# midi_footswitch.net
KiCad netlist of a schematic drawn in EasyEDA Pro
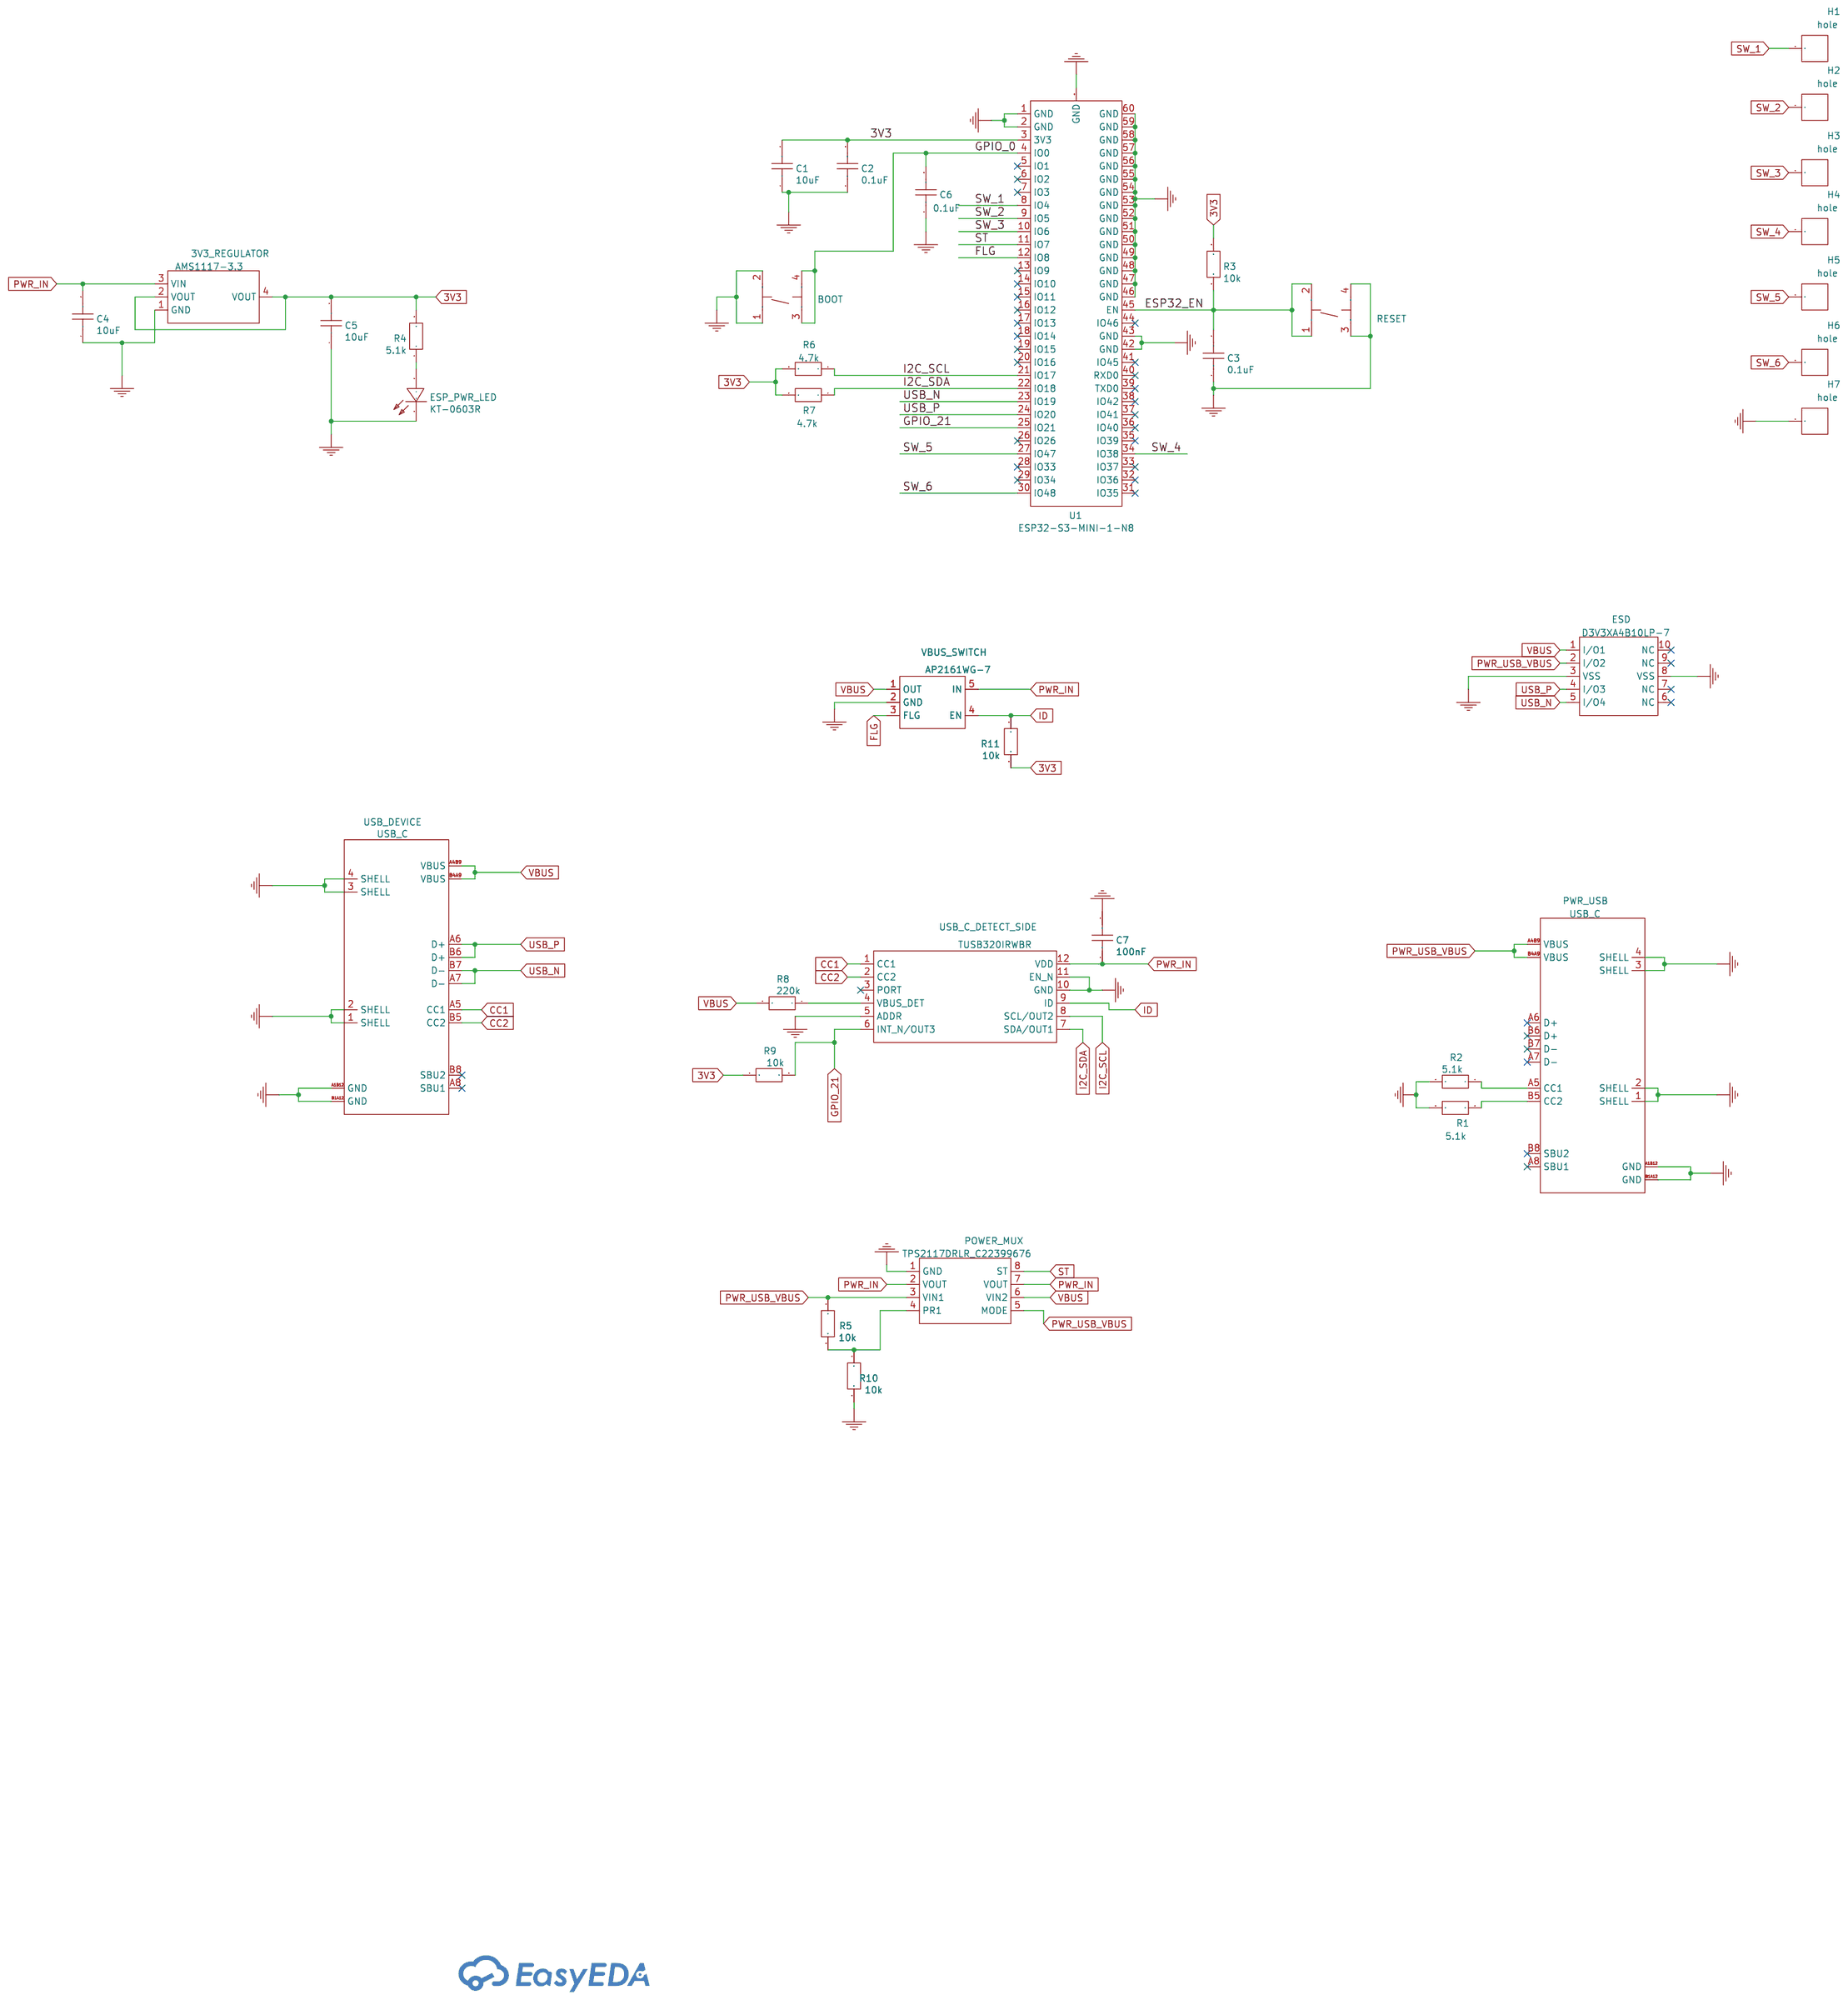
[diagram p0: schematic sheet]

(export (version "E")
  (design (tool "Eeschema 10.0.6"))
  (components
    (comp (ref "3V3_REGULATOR")
      (value "AMS1117-3.3")
      (footprint "easyedapro:SOT-223-3_L6.5-W3.4-P2.30-LS7.0-BR")
      (fields (field (name "Manufacturer") "AMS"))
      (libsource (lib "easyedapro") (part "AMS1117-3.3"))
    )
    (comp (ref "BOOT")
      (value "TS-1187A-B-A-B")
      (footprint "easyedapro:SW-SMD_4P-L5.1-W5.1-P3.70-LS6.5-TL_H1.5")
      (fields (field (name "Manufacturer") "XKB Connectivity(中国星坤)"))
      (libsource (lib "easyedapro") (part "TS-1187A-B-A-B"))
    )
    (comp (ref "C1")
      (value "10uF")
      (footprint "easyedapro:C0603")
      (libsource (lib "easyedapro") (part "10uF"))
    )
    (comp (ref "C2")
      (value "0.1uF")
      (footprint "easyedapro:C0603")
      (libsource (lib "easyedapro") (part "0.1uF"))
    )
    (comp (ref "C3")
      (value "0.1uF")
      (footprint "easyedapro:C0603")
      (libsource (lib "easyedapro") (part "0.1uF"))
    )
    (comp (ref "C4")
      (value "10uF")
      (footprint "easyedapro:C0603")
      (libsource (lib "easyedapro") (part "10uF"))
    )
    (comp (ref "C5")
      (value "10uF")
      (footprint "easyedapro:C0603")
      (libsource (lib "easyedapro") (part "10uF"))
    )
    (comp (ref "C6")
      (value "0.1uF")
      (footprint "easyedapro:C0603")
      (libsource (lib "easyedapro") (part "0.1uF"))
    )
    (comp (ref "C7")
      (value "100nF")
      (footprint "easyedapro:C0603")
      (libsource (lib "easyedapro") (part "100nF"))
    )
    (comp (ref "ESD")
      (value "D3V3XA4B10LP-7")
      (footprint "easyedapro:U-DFN2510-10_L2.5-W1.0-P0.50-BL")
      (fields (field (name "Manufacturer") "DIODES(美台)"))
      (libsource (lib "easyedapro") (part "D3V3XA4B10LP-7"))
    )
    (comp (ref "ESP_PWR_LED")
      (value "KT-0603R")
      (footprint "easyedapro:LED0603-RD")
      (fields (field (name "Manufacturer") "KENTO"))
      (libsource (lib "easyedapro") (part "KT-0603R"))
    )
    (comp (ref "H1")
      (value "hole")
      (footprint "easyedapro:HOLE_FOOTPRITNG")
      (libsource (lib "easyedapro") (part "hole"))
    )
    (comp (ref "H2")
      (value "hole")
      (footprint "easyedapro:HOLE_FOOTPRITNG")
      (libsource (lib "easyedapro") (part "hole"))
    )
    (comp (ref "H3")
      (value "hole")
      (footprint "easyedapro:HOLE_FOOTPRITNG")
      (libsource (lib "easyedapro") (part "hole"))
    )
    (comp (ref "H4")
      (value "hole")
      (footprint "easyedapro:HOLE_FOOTPRITNG")
      (libsource (lib "easyedapro") (part "hole"))
    )
    (comp (ref "H5")
      (value "hole")
      (footprint "easyedapro:HOLE_FOOTPRITNG")
      (libsource (lib "easyedapro") (part "hole"))
    )
    (comp (ref "H6")
      (value "hole")
      (footprint "easyedapro:HOLE_FOOTPRITNG")
      (libsource (lib "easyedapro") (part "hole"))
    )
    (comp (ref "H7")
      (value "hole")
      (footprint "easyedapro:HOLE_FOOTPRITNG")
      (libsource (lib "easyedapro") (part "hole"))
    )
    (comp (ref "POWER_MUX")
      (value "TPS2117DRLR_C22399676")
      (footprint "easyedapro:SOT-583-8_L2.1-W1.2-P0.50-LS1.6-BL")
      (fields (field (name "Manufacturer Part") "TPS2117DRLR") (field (name "Manufacturer") "TI(德州仪器)"))
      (libsource (lib "easyedapro") (part "TPS2117DRLR_C22399676"))
    )
    (comp (ref "PWR_USB")
      (value "USB_C")
      (footprint "easyedapro:USB-C-SMD_G-SWITCH_GT-USB-7010EN")
      (fields
        (field (name "Manufacturer Part") "HC-TYPE-C-16P-01A-R")
        (field (name "Manufacturer") "HCTL(华灿天禄)")
      )
      (libsource (lib "") (part "USB_C_1"))
    )
    (comp (ref "R1")
      (value "5.1k")
      (footprint "easyedapro:R0603")
      (libsource (lib "easyedapro") (part "5.1k"))
    )
    (comp (ref "R2")
      (value "5.1k")
      (footprint "easyedapro:R0603")
      (libsource (lib "easyedapro") (part "5.1k"))
    )
    (comp (ref "R3") (value "10k") (footprint "easyedapro:R0603") (libsource (lib "") (part "10k_1")))
    (comp (ref "R4") (value "5.1k") (footprint "easyedapro:R0603") (libsource (lib "") (part "5.1k_1")))
    (comp (ref "R5") (value "10k") (footprint "easyedapro:R0603") (libsource (lib "easyedapro") (part "10k")))
    (comp (ref "R6")
      (value "4.7k")
      (footprint "easyedapro:R0603")
      (libsource (lib "easyedapro") (part "4.7k"))
    )
    (comp (ref "R7")
      (value "4.7k")
      (footprint "easyedapro:R0603")
      (libsource (lib "easyedapro") (part "4.7k"))
    )
    (comp (ref "R8")
      (value "220k")
      (footprint "easyedapro:R0603")
      (libsource (lib "easyedapro") (part "220k"))
    )
    (comp (ref "R9") (value "10k") (footprint "easyedapro:R0603") (libsource (lib "") (part "10k_2")))
    (comp (ref "R10")
      (value "10k")
      (footprint "easyedapro:R0603")
      (libsource (lib "easyedapro") (part "10k"))
    )
    (comp (ref "R11")
      (value "10k")
      (footprint "easyedapro:R0603")
      (libsource (lib "easyedapro") (part "10k"))
    )
    (comp (ref "RESET")
      (value "TS-1187A-B-A-B")
      (footprint "easyedapro:SW-SMD_4P-L5.1-W5.1-P3.70-LS6.5-TL_H1.5")
      (fields (field (name "Manufacturer") "XKB Connectivity(中国星坤)"))
      (libsource (lib "easyedapro") (part "TS-1187A-B-A-B"))
    )
    (comp (ref "U1")
      (value "ESP32-S3-MINI-1-N8")
      (footprint "easyedapro:BULETM-SMD_ESP32-S3-MINI-1-N8")
      (fields (field (name "Manufacturer") "ESPRESSIF(乐鑫)"))
      (libsource (lib "easyedapro") (part "ESP32-S3-MINI-1-N8"))
    )
    (comp (ref "USB_C_DETECT_SIDE")
      (value "TUSB320IRWBR")
      (footprint "easyedapro:X2QFN-12_L1.6-W1.6-P0.40-TL")
      (fields (field (name "Manufacturer") "TI(德州仪器)"))
      (libsource (lib "easyedapro") (part "TUSB320IRWBR"))
    )
    (comp (ref "USB_DEVICE")
      (value "USB_C")
      (footprint "easyedapro:USB-C-SMD_G-SWITCH_GT-USB-7010EN")
      (fields
        (field (name "Manufacturer Part") "HC-TYPE-C-16P-01A-R")
        (field (name "Manufacturer") "HCTL(华灿天禄)")
      )
      (libsource (lib "easyedapro") (part "USB_C"))
    )
    (comp (ref "VBUS_SWITCH")
      (value "AP2161WG-7")
      (footprint "easyedapro:SOT-23-5_L2.9-W1.6-P0.95-LS2.8-BL")
      (fields (field (name "Manufacturer") "DIODES(美台)"))
      (libsource (lib "easyedapro") (part "AP2161WG-7"))
    )
  )
  (nets
    (net (code "1") (name "/ESP32_EN") (class "Default")
      (node (ref "C3") (pin "2") (pinfunction "2_2") (pintype "unspecified"))
      (node (ref "R3") (pin "1") (pinfunction "1_1") (pintype "unspecified"))
      (node (ref "RESET") (pin "1") (pinfunction "A_1") (pintype "unspecified"))
      (node (ref "RESET") (pin "2") (pinfunction "B_2") (pintype "unspecified"))
      (node (ref "U1") (pin "45") (pinfunction "EN_45") (pintype "unspecified"))
    )
    (net (code "2") (name "/GPIO_0") (class "Default")
      (node (ref "BOOT") (pin "3") (pinfunction "C_3") (pintype "unspecified"))
      (node (ref "BOOT") (pin "4") (pinfunction "D_4") (pintype "unspecified"))
      (node (ref "C6") (pin "2") (pinfunction "2_2") (pintype "unspecified"))
      (node (ref "U1") (pin "4") (pinfunction "IO0_4") (pintype "unspecified"))
    )
    (net (code "3") (name "3V3") (class "Default")
      (node (ref "3V3_REGULATOR") (pin "2") (pinfunction "VOUT_2") (pintype "unspecified"))
      (node (ref "3V3_REGULATOR") (pin "4") (pinfunction "VOUT_4") (pintype "unspecified"))
      (node (ref "C1") (pin "2") (pinfunction "2_2") (pintype "unspecified"))
      (node (ref "C2") (pin "2") (pinfunction "2_2") (pintype "unspecified"))
      (node (ref "C5") (pin "2") (pinfunction "2_2") (pintype "unspecified"))
      (node (ref "R11") (pin "2") (pinfunction "2_2") (pintype "unspecified"))
      (node (ref "R3") (pin "2") (pinfunction "2_2") (pintype "unspecified"))
      (node (ref "R4") (pin "2") (pinfunction "2_2") (pintype "unspecified"))
      (node (ref "R6") (pin "2") (pinfunction "2_2") (pintype "unspecified"))
      (node (ref "R7") (pin "2") (pinfunction "2_2") (pintype "unspecified"))
      (node (ref "R9") (pin "1") (pinfunction "1_1") (pintype "unspecified"))
      (node (ref "U1") (pin "3") (pinfunction "3V3_3") (pintype "unspecified"))
    )
    (net (code "4") (name "CC1") (class "Default")
      (node (ref "USB_C_DETECT_SIDE") (pin "1") (pinfunction "CC1_1") (pintype "unspecified"))
      (node (ref "USB_DEVICE") (pin "A5") (pinfunction "CC1_A5") (pintype "unspecified"))
    )
    (net (code "5") (name "CC2") (class "Default")
      (node (ref "USB_C_DETECT_SIDE") (pin "2") (pinfunction "CC2_2") (pintype "unspecified"))
      (node (ref "USB_DEVICE") (pin "B5") (pinfunction "CC2_B5") (pintype "unspecified"))
    )
    (net (code "6") (name "FLG") (class "Default")
      (node (ref "U1") (pin "12") (pinfunction "IO8_12") (pintype "unspecified"))
      (node (ref "VBUS_SWITCH") (pin "3") (pinfunction "FLG_3") (pintype "unspecified"))
    )
    (net (code "7") (name "GND") (class "Default")
      (node (ref "3V3_REGULATOR") (pin "1") (pinfunction "GND_1") (pintype "unspecified"))
      (node (ref "BOOT") (pin "1") (pinfunction "A_1") (pintype "unspecified"))
      (node (ref "BOOT") (pin "2") (pinfunction "B_2") (pintype "unspecified"))
      (node (ref "C1") (pin "1") (pinfunction "1_1") (pintype "unspecified"))
      (node (ref "C2") (pin "1") (pinfunction "1_1") (pintype "unspecified"))
      (node (ref "C3") (pin "1") (pinfunction "1_1") (pintype "unspecified"))
      (node (ref "C4") (pin "1") (pinfunction "1_1") (pintype "unspecified"))
      (node (ref "C5") (pin "1") (pinfunction "1_1") (pintype "unspecified"))
      (node (ref "C6") (pin "1") (pinfunction "1_1") (pintype "unspecified"))
      (node (ref "C7") (pin "2") (pinfunction "2_2") (pintype "unspecified"))
      (node (ref "ESD") (pin "3") (pinfunction "VSS_3") (pintype "unspecified"))
      (node (ref "ESD") (pin "8") (pinfunction "VSS_8") (pintype "unspecified"))
      (node (ref "ESP_PWR_LED") (pin "1") (pinfunction "K_1") (pintype "unspecified"))
      (node (ref "H7") (pin "1") (pinfunction "1_1") (pintype "bidirectional"))
      (node (ref "POWER_MUX") (pin "1") (pinfunction "GND_1") (pintype "unspecified"))
      (node (ref "PWR_USB") (pin "1") (pinfunction "SHELL_1") (pintype "unspecified"))
      (node (ref "PWR_USB") (pin "2") (pinfunction "SHELL_2") (pintype "unspecified"))
      (node (ref "PWR_USB") (pin "3") (pinfunction "SHELL_3") (pintype "unspecified"))
      (node (ref "PWR_USB") (pin "4") (pinfunction "SHELL_4") (pintype "unspecified"))
      (node (ref "PWR_USB") (pin "A1B12") (pinfunction "GND_A1B12") (pintype "unspecified"))
      (node (ref "PWR_USB") (pin "B1A12") (pinfunction "GND_B1A12") (pintype "unspecified"))
      (node (ref "R1") (pin "2") (pinfunction "2_2") (pintype "unspecified"))
      (node (ref "R10") (pin "2") (pinfunction "2_2") (pintype "unspecified"))
      (node (ref "R2") (pin "2") (pinfunction "2_2") (pintype "unspecified"))
      (node (ref "RESET") (pin "3") (pinfunction "C_3") (pintype "unspecified"))
      (node (ref "RESET") (pin "4") (pinfunction "D_4") (pintype "unspecified"))
      (node (ref "U1") (pin "1") (pinfunction "GND_1") (pintype "unspecified"))
      (node (ref "U1") (pin "2") (pinfunction "GND_2") (pintype "unspecified"))
      (node (ref "U1") (pin "42") (pinfunction "GND_42") (pintype "unspecified"))
      (node (ref "U1") (pin "43") (pinfunction "GND_43") (pintype "unspecified"))
      (node (ref "U1") (pin "46") (pinfunction "GND_46") (pintype "unspecified"))
      (node (ref "U1") (pin "47") (pinfunction "GND_47") (pintype "unspecified"))
      (node (ref "U1") (pin "48") (pinfunction "GND_48") (pintype "unspecified"))
      (node (ref "U1") (pin "49") (pinfunction "GND_49") (pintype "unspecified"))
      (node (ref "U1") (pin "50") (pinfunction "GND_50") (pintype "unspecified"))
      (node (ref "U1") (pin "51") (pinfunction "GND_51") (pintype "unspecified"))
      (node (ref "U1") (pin "52") (pinfunction "GND_52") (pintype "unspecified"))
      (node (ref "U1") (pin "53") (pinfunction "GND_53") (pintype "unspecified"))
      (node (ref "U1") (pin "54") (pinfunction "GND_54") (pintype "unspecified"))
      (node (ref "U1") (pin "55") (pinfunction "GND_55") (pintype "unspecified"))
      (node (ref "U1") (pin "56") (pinfunction "GND_56") (pintype "unspecified"))
      (node (ref "U1") (pin "57") (pinfunction "GND_57") (pintype "unspecified"))
      (node (ref "U1") (pin "58") (pinfunction "GND_58") (pintype "unspecified"))
      (node (ref "U1") (pin "59") (pinfunction "GND_59") (pintype "unspecified"))
      (node (ref "U1") (pin "60") (pinfunction "GND_60") (pintype "unspecified"))
      (node (ref "U1") (pin "GND") (pinfunction "GND_GND") (pintype "unspecified"))
      (node (ref "USB_C_DETECT_SIDE") (pin "10") (pinfunction "GND_10") (pintype "unspecified"))
      (node (ref "USB_C_DETECT_SIDE") (pin "11") (pinfunction "EN_N_11") (pintype "unspecified"))
      (node (ref "USB_C_DETECT_SIDE") (pin "5") (pinfunction "ADDR_5") (pintype "unspecified"))
      (node (ref "USB_DEVICE") (pin "1") (pinfunction "SHELL_1") (pintype "unspecified"))
      (node (ref "USB_DEVICE") (pin "2") (pinfunction "SHELL_2") (pintype "unspecified"))
      (node (ref "USB_DEVICE") (pin "3") (pinfunction "SHELL_3") (pintype "unspecified"))
      (node (ref "USB_DEVICE") (pin "4") (pinfunction "SHELL_4") (pintype "unspecified"))
      (node (ref "USB_DEVICE") (pin "A1B12") (pinfunction "GND_A1B12") (pintype "unspecified"))
      (node (ref "USB_DEVICE") (pin "B1A12") (pinfunction "GND_B1A12") (pintype "unspecified"))
      (node (ref "VBUS_SWITCH") (pin "2") (pinfunction "GND_2") (pintype "unspecified"))
    )
    (net (code "8") (name "GPIO_21") (class "Default")
      (node (ref "R9") (pin "2") (pinfunction "2_2") (pintype "unspecified"))
      (node (ref "U1") (pin "25") (pinfunction "IO21_25") (pintype "unspecified"))
      (node (ref "USB_C_DETECT_SIDE") (pin "6") (pinfunction "INT_N/OUT3_6") (pintype "unspecified"))
    )
    (net (code "9") (name "I2C_SCL") (class "Default")
      (node (ref "R6") (pin "1") (pinfunction "1_1") (pintype "unspecified"))
      (node (ref "U1") (pin "21") (pinfunction "IO17_21") (pintype "unspecified"))
      (node (ref "USB_C_DETECT_SIDE") (pin "8") (pinfunction "SCL/OUT2_8") (pintype "unspecified"))
    )
    (net (code "10") (name "I2C_SDA") (class "Default")
      (node (ref "R7") (pin "1") (pinfunction "1_1") (pintype "unspecified"))
      (node (ref "U1") (pin "22") (pinfunction "IO18_22") (pintype "unspecified"))
      (node (ref "USB_C_DETECT_SIDE") (pin "7") (pinfunction "SDA/OUT1_7") (pintype "unspecified"))
    )
    (net (code "11") (name "ID") (class "Default")
      (node (ref "R11") (pin "1") (pinfunction "1_1") (pintype "unspecified"))
      (node (ref "USB_C_DETECT_SIDE") (pin "9") (pinfunction "ID_9") (pintype "unspecified"))
      (node (ref "VBUS_SWITCH") (pin "4") (pinfunction "EN_4") (pintype "unspecified"))
    )
    (net (code "12") (name "Net-(ESP_PWR_LED-A)") (class "Default")
      (node (ref "ESP_PWR_LED") (pin "2") (pinfunction "A_2") (pintype "unspecified"))
      (node (ref "R4") (pin "1") (pinfunction "1_1") (pintype "unspecified"))
    )
    (net (code "13") (name "Net-(POWER_MUX-PR1)") (class "Default")
      (node (ref "POWER_MUX") (pin "4") (pinfunction "PR1_4") (pintype "unspecified"))
      (node (ref "R10") (pin "1") (pinfunction "1_1") (pintype "unspecified"))
      (node (ref "R5") (pin "2") (pinfunction "2_2") (pintype "unspecified"))
    )
    (net (code "14") (name "Net-(PWR_USB-CC1)") (class "Default")
      (node (ref "PWR_USB") (pin "A5") (pinfunction "CC1_A5") (pintype "unspecified"))
      (node (ref "R2") (pin "1") (pinfunction "1_1") (pintype "unspecified"))
    )
    (net (code "15") (name "Net-(PWR_USB-CC2)") (class "Default")
      (node (ref "PWR_USB") (pin "B5") (pinfunction "CC2_B5") (pintype "unspecified"))
      (node (ref "R1") (pin "1") (pinfunction "1_1") (pintype "unspecified"))
    )
    (net (code "16") (name "Net-(USB_C_DETECT_SIDE-VBUS_DET)") (class "Default")
      (node (ref "R8") (pin "1") (pinfunction "1_1") (pintype "unspecified"))
      (node (ref "USB_C_DETECT_SIDE") (pin "4") (pinfunction "VBUS_DET_4") (pintype "unspecified"))
    )
    (net (code "17") (name "PWR_IN") (class "Default")
      (node (ref "3V3_REGULATOR") (pin "3") (pinfunction "VIN_3") (pintype "unspecified"))
      (node (ref "C4") (pin "2") (pinfunction "2_2") (pintype "unspecified"))
      (node (ref "C7") (pin "1") (pinfunction "1_1") (pintype "unspecified"))
      (node (ref "POWER_MUX") (pin "2") (pinfunction "VOUT_2") (pintype "unspecified"))
      (node (ref "POWER_MUX") (pin "7") (pinfunction "VOUT_7") (pintype "unspecified"))
      (node (ref "USB_C_DETECT_SIDE") (pin "12") (pinfunction "VDD_12") (pintype "unspecified"))
      (node (ref "VBUS_SWITCH") (pin "5") (pinfunction "IN_5") (pintype "unspecified"))
    )
    (net (code "18") (name "PWR_USB_VBUS") (class "Default")
      (node (ref "ESD") (pin "2") (pinfunction "I/O2_2") (pintype "unspecified"))
      (node (ref "POWER_MUX") (pin "3") (pinfunction "VIN1_3") (pintype "unspecified"))
      (node (ref "POWER_MUX") (pin "5") (pinfunction "MODE_5") (pintype "unspecified"))
      (node (ref "PWR_USB") (pin "A4B9") (pinfunction "VBUS_A4B9") (pintype "unspecified"))
      (node (ref "PWR_USB") (pin "B4A9") (pinfunction "VBUS_B4A9") (pintype "unspecified"))
      (node (ref "R5") (pin "1") (pinfunction "1_1") (pintype "unspecified"))
    )
    (net (code "19") (name "ST") (class "Default")
      (node (ref "POWER_MUX") (pin "8") (pinfunction "ST_8") (pintype "unspecified"))
      (node (ref "U1") (pin "11") (pinfunction "IO7_11") (pintype "unspecified"))
    )
    (net (code "20") (name "SW_1") (class "Default")
      (node (ref "H1") (pin "1") (pinfunction "1_1") (pintype "bidirectional"))
      (node (ref "U1") (pin "8") (pinfunction "IO4_8") (pintype "unspecified"))
    )
    (net (code "21") (name "SW_2") (class "Default")
      (node (ref "H2") (pin "1") (pinfunction "1_1") (pintype "bidirectional"))
      (node (ref "U1") (pin "9") (pinfunction "IO5_9") (pintype "unspecified"))
    )
    (net (code "22") (name "SW_3") (class "Default")
      (node (ref "H3") (pin "1") (pinfunction "1_1") (pintype "bidirectional"))
      (node (ref "U1") (pin "10") (pinfunction "IO6_10") (pintype "unspecified"))
    )
    (net (code "23") (name "SW_4") (class "Default")
      (node (ref "H4") (pin "1") (pinfunction "1_1") (pintype "bidirectional"))
      (node (ref "U1") (pin "34") (pinfunction "IO38_34") (pintype "unspecified"))
    )
    (net (code "24") (name "SW_5") (class "Default")
      (node (ref "H5") (pin "1") (pinfunction "1_1") (pintype "bidirectional"))
      (node (ref "U1") (pin "27") (pinfunction "IO47_27") (pintype "unspecified"))
    )
    (net (code "25") (name "SW_6") (class "Default")
      (node (ref "H6") (pin "1") (pinfunction "1_1") (pintype "bidirectional"))
      (node (ref "U1") (pin "30") (pinfunction "IO48_30") (pintype "unspecified"))
    )
    (net (code "26") (name "USB_N") (class "Default")
      (node (ref "ESD") (pin "5") (pinfunction "I/O4_5") (pintype "unspecified"))
      (node (ref "U1") (pin "23") (pinfunction "IO19_23") (pintype "unspecified"))
      (node (ref "USB_DEVICE") (pin "A7") (pinfunction "D-_A7") (pintype "unspecified"))
      (node (ref "USB_DEVICE") (pin "B7") (pinfunction "D-_B7") (pintype "unspecified"))
    )
    (net (code "27") (name "USB_P") (class "Default")
      (node (ref "ESD") (pin "4") (pinfunction "I/O3_4") (pintype "unspecified"))
      (node (ref "U1") (pin "24") (pinfunction "IO20_24") (pintype "unspecified"))
      (node (ref "USB_DEVICE") (pin "A6") (pinfunction "D+_A6") (pintype "unspecified"))
      (node (ref "USB_DEVICE") (pin "B6") (pinfunction "D+_B6") (pintype "unspecified"))
    )
    (net (code "28") (name "VBUS") (class "Default")
      (node (ref "ESD") (pin "1") (pinfunction "I/O1_1") (pintype "unspecified"))
      (node (ref "POWER_MUX") (pin "6") (pinfunction "VIN2_6") (pintype "unspecified"))
      (node (ref "R8") (pin "2") (pinfunction "2_2") (pintype "unspecified"))
      (node (ref "USB_DEVICE") (pin "A4B9") (pinfunction "VBUS_A4B9") (pintype "unspecified"))
      (node (ref "USB_DEVICE") (pin "B4A9") (pinfunction "VBUS_B4A9") (pintype "unspecified"))
      (node (ref "VBUS_SWITCH") (pin "1") (pinfunction "OUT_1") (pintype "unspecified"))
    )
    (net (code "29") (name "unconnected-(ESD-NC-Pad6)") (class "Default")
      (node (ref "ESD") (pin "6") (pinfunction "NC_6") (pintype "unspecified+no_connect"))
    )
    (net (code "30") (name "unconnected-(ESD-NC-Pad7)") (class "Default")
      (node (ref "ESD") (pin "7") (pinfunction "NC_7") (pintype "unspecified+no_connect"))
    )
    (net (code "31") (name "unconnected-(ESD-NC-Pad9)") (class "Default")
      (node (ref "ESD") (pin "9") (pinfunction "NC_9") (pintype "unspecified+no_connect"))
    )
    (net (code "32") (name "unconnected-(ESD-NC-Pad10)") (class "Default")
      (node (ref "ESD") (pin "10") (pinfunction "NC_10") (pintype "unspecified+no_connect"))
    )
    (net (code "33") (name "unconnected-(PWR_USB-D+-PadA6)") (class "Default")
      (node (ref "PWR_USB") (pin "A6") (pinfunction "D+_A6") (pintype "unspecified+no_connect"))
    )
    (net (code "34") (name "unconnected-(PWR_USB-D+-PadB6)") (class "Default")
      (node (ref "PWR_USB") (pin "B6") (pinfunction "D+_B6") (pintype "unspecified+no_connect"))
    )
    (net (code "35") (name "unconnected-(PWR_USB-D--PadA7)") (class "Default")
      (node (ref "PWR_USB") (pin "A7") (pinfunction "D-_A7") (pintype "unspecified+no_connect"))
    )
    (net (code "36") (name "unconnected-(PWR_USB-D--PadB7)") (class "Default")
      (node (ref "PWR_USB") (pin "B7") (pinfunction "D-_B7") (pintype "unspecified+no_connect"))
    )
    (net (code "37") (name "unconnected-(PWR_USB-SBU1-PadA8)") (class "Default")
      (node (ref "PWR_USB") (pin "A8") (pinfunction "SBU1_A8") (pintype "unspecified+no_connect"))
    )
    (net (code "38") (name "unconnected-(PWR_USB-SBU2-PadB8)") (class "Default")
      (node (ref "PWR_USB") (pin "B8") (pinfunction "SBU2_B8") (pintype "unspecified+no_connect"))
    )
    (net (code "39") (name "unconnected-(U1-IO1-Pad5)") (class "Default")
      (node (ref "U1") (pin "5") (pinfunction "IO1_5") (pintype "unspecified+no_connect"))
    )
    (net (code "40") (name "unconnected-(U1-IO2-Pad6)") (class "Default")
      (node (ref "U1") (pin "6") (pinfunction "IO2_6") (pintype "unspecified+no_connect"))
    )
    (net (code "41") (name "unconnected-(U1-IO3-Pad7)") (class "Default")
      (node (ref "U1") (pin "7") (pinfunction "IO3_7") (pintype "unspecified+no_connect"))
    )
    (net (code "42") (name "unconnected-(U1-IO9-Pad13)") (class "Default")
      (node (ref "U1") (pin "13") (pinfunction "IO9_13") (pintype "unspecified+no_connect"))
    )
    (net (code "43") (name "unconnected-(U1-IO10-Pad14)") (class "Default")
      (node (ref "U1") (pin "14") (pinfunction "IO10_14") (pintype "unspecified+no_connect"))
    )
    (net (code "44") (name "unconnected-(U1-IO11-Pad15)") (class "Default")
      (node (ref "U1") (pin "15") (pinfunction "IO11_15") (pintype "unspecified+no_connect"))
    )
    (net (code "45") (name "unconnected-(U1-IO12-Pad16)") (class "Default")
      (node (ref "U1") (pin "16") (pinfunction "IO12_16") (pintype "unspecified+no_connect"))
    )
    (net (code "46") (name "unconnected-(U1-IO13-Pad17)") (class "Default")
      (node (ref "U1") (pin "17") (pinfunction "IO13_17") (pintype "unspecified+no_connect"))
    )
    (net (code "47") (name "unconnected-(U1-IO14-Pad18)") (class "Default")
      (node (ref "U1") (pin "18") (pinfunction "IO14_18") (pintype "unspecified+no_connect"))
    )
    (net (code "48") (name "unconnected-(U1-IO15-Pad19)") (class "Default")
      (node (ref "U1") (pin "19") (pinfunction "IO15_19") (pintype "unspecified+no_connect"))
    )
    (net (code "49") (name "unconnected-(U1-IO16-Pad20)") (class "Default")
      (node (ref "U1") (pin "20") (pinfunction "IO16_20") (pintype "unspecified+no_connect"))
    )
    (net (code "50") (name "unconnected-(U1-IO26-Pad26)") (class "Default")
      (node (ref "U1") (pin "26") (pinfunction "IO26_26") (pintype "unspecified+no_connect"))
    )
    (net (code "51") (name "unconnected-(U1-IO33-Pad28)") (class "Default")
      (node (ref "U1") (pin "28") (pinfunction "IO33_28") (pintype "unspecified+no_connect"))
    )
    (net (code "52") (name "unconnected-(U1-IO34-Pad29)") (class "Default")
      (node (ref "U1") (pin "29") (pinfunction "IO34_29") (pintype "unspecified+no_connect"))
    )
    (net (code "53") (name "unconnected-(U1-IO35-Pad31)") (class "Default")
      (node (ref "U1") (pin "31") (pinfunction "IO35_31") (pintype "unspecified+no_connect"))
    )
    (net (code "54") (name "unconnected-(U1-IO36-Pad32)") (class "Default")
      (node (ref "U1") (pin "32") (pinfunction "IO36_32") (pintype "unspecified+no_connect"))
    )
    (net (code "55") (name "unconnected-(U1-IO37-Pad33)") (class "Default")
      (node (ref "U1") (pin "33") (pinfunction "IO37_33") (pintype "unspecified+no_connect"))
    )
    (net (code "56") (name "unconnected-(U1-IO39-Pad35)") (class "Default")
      (node (ref "U1") (pin "35") (pinfunction "IO39_35") (pintype "unspecified+no_connect"))
    )
    (net (code "57") (name "unconnected-(U1-IO40-Pad36)") (class "Default")
      (node (ref "U1") (pin "36") (pinfunction "IO40_36") (pintype "unspecified+no_connect"))
    )
    (net (code "58") (name "unconnected-(U1-IO41-Pad37)") (class "Default")
      (node (ref "U1") (pin "37") (pinfunction "IO41_37") (pintype "unspecified+no_connect"))
    )
    (net (code "59") (name "unconnected-(U1-IO42-Pad38)") (class "Default")
      (node (ref "U1") (pin "38") (pinfunction "IO42_38") (pintype "unspecified+no_connect"))
    )
    (net (code "60") (name "unconnected-(U1-IO45-Pad41)") (class "Default")
      (node (ref "U1") (pin "41") (pinfunction "IO45_41") (pintype "unspecified+no_connect"))
    )
    (net (code "61") (name "unconnected-(U1-IO46-Pad44)") (class "Default")
      (node (ref "U1") (pin "44") (pinfunction "IO46_44") (pintype "unspecified+no_connect"))
    )
    (net (code "62") (name "unconnected-(U1-RXD0-Pad40)") (class "Default")
      (node (ref "U1") (pin "40") (pinfunction "RXD0_40") (pintype "unspecified+no_connect"))
    )
    (net (code "63") (name "unconnected-(U1-TXD0-Pad39)") (class "Default")
      (node (ref "U1") (pin "39") (pinfunction "TXD0_39") (pintype "unspecified+no_connect"))
    )
    (net (code "64") (name "unconnected-(USB_C_DETECT_SIDE-PORT-Pad3)") (class "Default")
      (node (ref "USB_C_DETECT_SIDE") (pin "3") (pinfunction "PORT_3") (pintype "unspecified+no_connect"))
    )
    (net (code "65") (name "unconnected-(USB_DEVICE-SBU1-PadA8)") (class "Default")
      (node (ref "USB_DEVICE") (pin "A8") (pinfunction "SBU1_A8") (pintype "unspecified+no_connect"))
    )
    (net (code "66") (name "unconnected-(USB_DEVICE-SBU2-PadB8)") (class "Default")
      (node (ref "USB_DEVICE") (pin "B8") (pinfunction "SBU2_B8") (pintype "unspecified+no_connect"))
    )
  )
)
